# 03-PeripheralPart-V2_1.net
KiCad netlist of a schematic drawn in Altium Designer
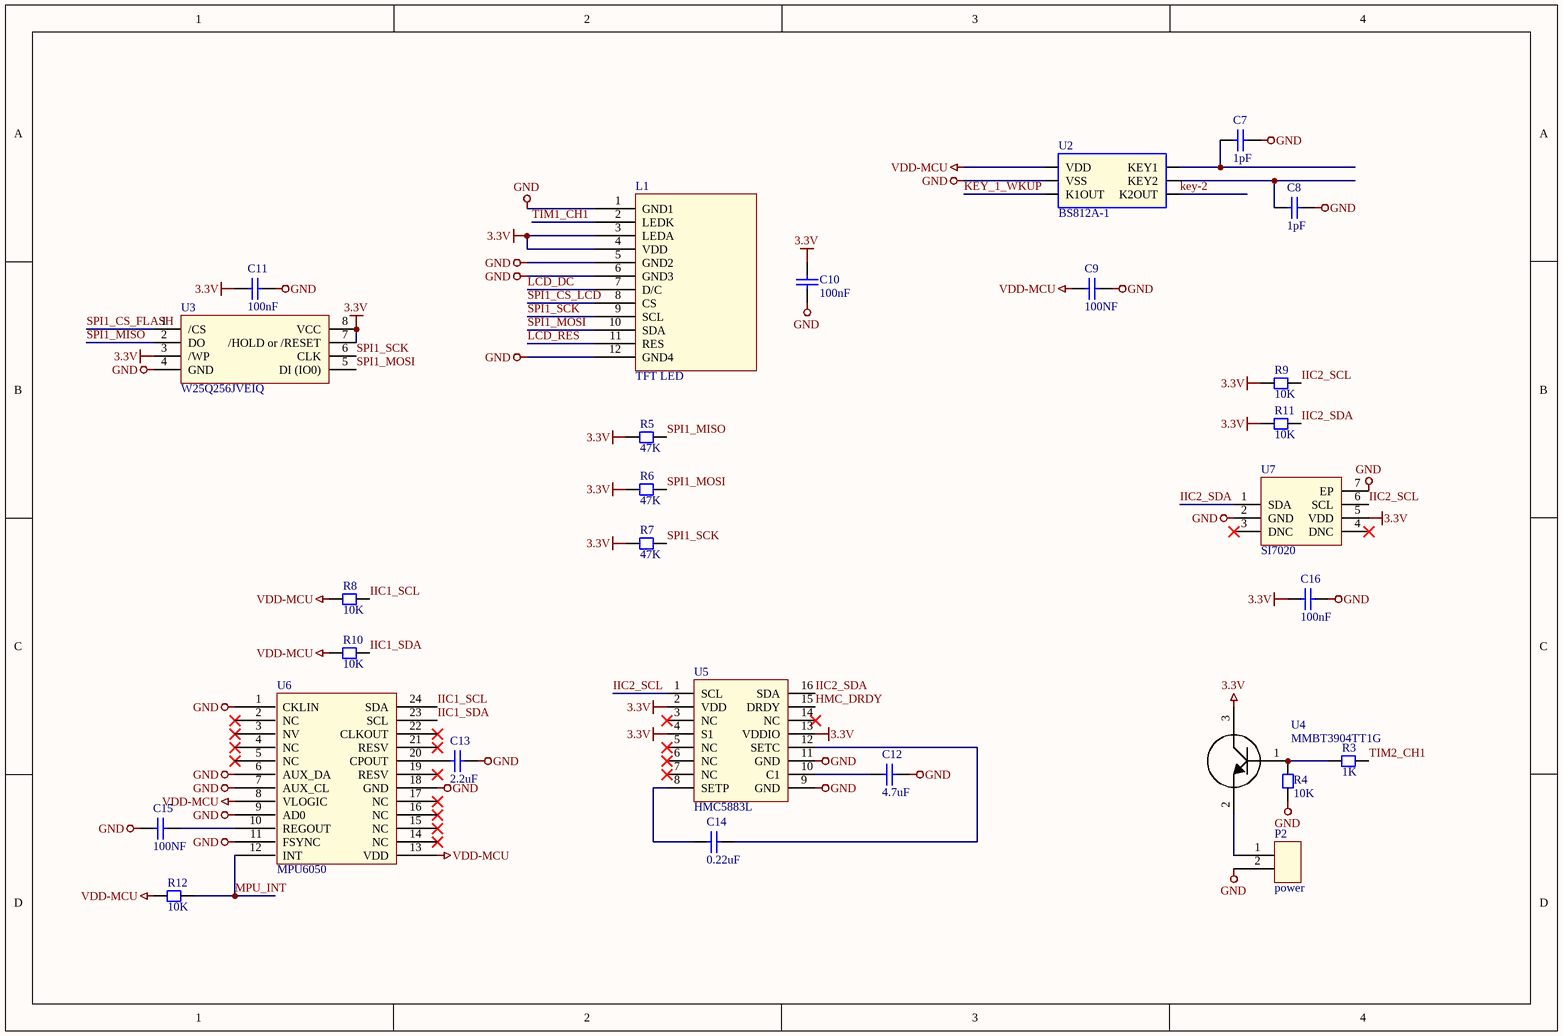
[diagram p0: 03-PeripheralPart-V2.1.SchDoc]

(export (version "E")
  (design (tool "Eeschema 10.0.6"))
  (components
    (comp (ref "C7")
      (value "1pF")
      (footprint "CC1005-0402")
      (description "贴片电容")
      (libsource (lib "tianxiaohua_Schlib") (part "Chip capacitor"))
    )
    (comp (ref "C8")
      (value "1pF")
      (footprint "CC1005-0402")
      (description "贴片电容")
      (libsource (lib "tianxiaohua_Schlib") (part "Chip capacitor"))
    )
    (comp (ref "C9")
      (value "100NF")
      (footprint "CC1005-0402")
      (description "贴片电容")
      (libsource (lib "tianxiaohua_Schlib") (part "Chip capacitor"))
    )
    (comp (ref "C10")
      (value "100nF")
      (footprint "CC1005-0402")
      (description "贴片电容")
      (libsource (lib "tianxiaohua_Schlib") (part "Chip capacitor"))
    )
    (comp (ref "C11")
      (value "100nF")
      (footprint "CC1005-0402")
      (description "贴片电容")
      (libsource (lib "tianxiaohua_Schlib") (part "Chip capacitor"))
    )
    (comp (ref "C12")
      (value "4.7uF")
      (footprint "CC1005-0402")
      (description "贴片电容")
      (libsource (lib "tianxiaohua_Schlib") (part "Chip capacitor"))
    )
    (comp (ref "C13")
      (value "2.2uF")
      (footprint "CC1005-0402")
      (description "贴片电容")
      (libsource (lib "tianxiaohua_Schlib") (part "Chip capacitor"))
    )
    (comp (ref "C14")
      (value "0.22uF")
      (footprint "CC1005-0402")
      (description "贴片电容")
      (libsource (lib "tianxiaohua_Schlib") (part "Chip capacitor"))
    )
    (comp (ref "C15")
      (value "100NF")
      (footprint "CC1005-0402")
      (description "贴片电容")
      (libsource (lib "tianxiaohua_Schlib") (part "Chip capacitor"))
    )
    (comp (ref "C16")
      (value "100nF")
      (footprint "CC1005-0402")
      (description "贴片电容")
      (libsource (lib "tianxiaohua_Schlib") (part "Chip capacitor"))
    )
    (comp (ref "L1")
      (value "TFT LED")
      (footprint "LCD-1.3-(2)")
      (description "1.3寸显示屏幕")
      (libsource (lib "tianxiaohua_Schlib") (part "LCD-IPSscreen-1.3"))
    )
    (comp (ref "P2")
      (value "power")
      (footprint "POWER-3.7V")
      (libsource (lib "tianxiaohua_Schlib") (part "power"))
    )
    (comp (ref "R3")
      (value "1K")
      (footprint "CR1005-0402")
      (description "贴片电阻")
      (libsource (lib "tianxiaohua_Schlib") (part "Chip resistor"))
    )
    (comp (ref "R4")
      (value "10K")
      (footprint "CR1005-0402")
      (description "贴片电阻")
      (libsource (lib "") (part "Chip resistor_1"))
    )
    (comp (ref "R5")
      (value "47K")
      (footprint "CR1005-0402")
      (description "贴片电阻")
      (libsource (lib "tianxiaohua_Schlib") (part "Chip resistor"))
    )
    (comp (ref "R6")
      (value "47K")
      (footprint "CR1005-0402")
      (description "贴片电阻")
      (libsource (lib "tianxiaohua_Schlib") (part "Chip resistor"))
    )
    (comp (ref "R7")
      (value "47K")
      (footprint "CR1005-0402")
      (description "贴片电阻")
      (libsource (lib "tianxiaohua_Schlib") (part "Chip resistor"))
    )
    (comp (ref "R8")
      (value "10K")
      (footprint "CR1005-0402")
      (description "贴片电阻")
      (libsource (lib "tianxiaohua_Schlib") (part "Chip resistor"))
    )
    (comp (ref "R9")
      (value "10K")
      (footprint "CR1005-0402")
      (description "贴片电阻")
      (libsource (lib "tianxiaohua_Schlib") (part "Chip resistor"))
    )
    (comp (ref "R10")
      (value "10K")
      (footprint "CR1005-0402")
      (description "贴片电阻")
      (libsource (lib "tianxiaohua_Schlib") (part "Chip resistor"))
    )
    (comp (ref "R11")
      (value "10K")
      (footprint "CR1005-0402")
      (description "贴片电阻")
      (libsource (lib "tianxiaohua_Schlib") (part "Chip resistor"))
    )
    (comp (ref "R12")
      (value "10K")
      (footprint "CR1005-0402")
      (description "贴片电阻")
      (libsource (lib "tianxiaohua_Schlib") (part "Chip resistor"))
    )
    (comp (ref "U2")
      (value "BS812A-1")
      (footprint "SOT23-6")
      (description "触摸按键 两路 SOP23-6封装极简电路")
      (libsource (lib "tianxiaohua_Schlib") (part "BS812A-1"))
    )
    (comp (ref "U3")
      (value "W25Q256JVEIQ")
      (footprint "WSON-8_L8.0-W6.10-P1.27-TL-EP")
      (description "FLASH")
      (libsource (lib "tianxiaohua_Schlib") (part "W25Q256JVEIQ"))
    )
    (comp (ref "U4")
      (value "MMBT3904TT1G")
      (footprint "SOT-416")
      (description "NPN 电流 - 集电极（Ic）（最大值）：200mA 电压 - 集射极击穿（最大值）：40V SOT-23-3")
      (libsource (lib "tianxiaohua_Schlib") (part "MMBT3904TT1G"))
    )
    (comp (ref "U5")
      (value "HMC5883L")
      (footprint "LPCC-16_L3.0-W3.0-P0.50-BL")
      (description "三轴罗盘")
      (libsource (lib "tianxiaohua_Schlib") (part "HMC5883L"))
    )
    (comp (ref "U6")
      (value "MPU6050")
      (footprint "QFN24 - duplicate")
      (description "陀螺仪")
      (libsource (lib "tianxiaohua_Schlib") (part "MPU6050"))
    )
    (comp (ref "U7")
      (value "SI7020")
      (footprint "DFN-6")
      (description "温湿度传感器芯片")
      (libsource (lib "tianxiaohua_Schlib") (part "SI7020"))
    )
  )
  (nets
    (net (code "1") (name "/HMC_DRDY") (class "Default")
      (node (ref "U5") (pin "15") (pinfunction "DRDY_15") (pintype "passive"))
    )
    (net (code "2") (name "/IIC1_SCL") (class "Default")
      (node (ref "R8") (pin "1") (pinfunction "1_1") (pintype "passive"))
      (node (ref "U6") (pin "24") (pinfunction "SDA_24") (pintype "passive"))
    )
    (net (code "3") (name "/IIC1_SDA") (class "Default")
      (node (ref "R10") (pin "1") (pinfunction "1_1") (pintype "passive"))
      (node (ref "U6") (pin "23") (pinfunction "SCL_23") (pintype "passive"))
    )
    (net (code "4") (name "/IIC2_SCL") (class "Default")
      (node (ref "R9") (pin "1") (pinfunction "1_1") (pintype "passive"))
      (node (ref "U5") (pin "1") (pinfunction "SCL_1") (pintype "passive"))
      (node (ref "U7") (pin "6") (pinfunction "SCL_6") (pintype "passive"))
    )
    (net (code "5") (name "/IIC2_SDA") (class "Default")
      (node (ref "R11") (pin "1") (pinfunction "1_1") (pintype "passive"))
      (node (ref "U5") (pin "16") (pinfunction "SDA_16") (pintype "passive"))
      (node (ref "U7") (pin "1") (pinfunction "SDA_1") (pintype "passive"))
    )
    (net (code "6") (name "/KEY_1_WKUP") (class "Default")
      (node (ref "U2") (pin "3") (pinfunction "K1OUT_3") (pintype "passive"))
    )
    (net (code "7") (name "/LCD_DC") (class "Default")
      (node (ref "L1") (pin "7") (pinfunction "D/C_7") (pintype "passive"))
    )
    (net (code "8") (name "/LCD_RES") (class "Default")
      (node (ref "L1") (pin "11") (pinfunction "RES_11") (pintype "passive"))
    )
    (net (code "9") (name "/MPU_INT") (class "Default")
      (node (ref "R12") (pin "1") (pinfunction "1_1") (pintype "passive"))
      (node (ref "U6") (pin "12") (pinfunction "INT_12") (pintype "passive"))
    )
    (net (code "10") (name "/SPI1_CS_FLASH") (class "Default")
      (node (ref "U3") (pin "1") (pinfunction "/CS_1") (pintype "passive"))
    )
    (net (code "11") (name "/SPI1_CS_LCD") (class "Default")
      (node (ref "L1") (pin "8") (pinfunction "CS_8") (pintype "passive"))
    )
    (net (code "12") (name "/SPI1_MISO") (class "Default")
      (node (ref "R5") (pin "1") (pinfunction "1_1") (pintype "passive"))
      (node (ref "U3") (pin "2") (pinfunction "DO_2") (pintype "passive"))
    )
    (net (code "13") (name "/SPI1_MOSI") (class "Default")
      (node (ref "L1") (pin "10") (pinfunction "SDA_10") (pintype "passive"))
      (node (ref "R6") (pin "1") (pinfunction "1_1") (pintype "passive"))
      (node (ref "U3") (pin "5") (pinfunction "DI_(IO0)_5") (pintype "passive"))
    )
    (net (code "14") (name "/SPI1_SCK") (class "Default")
      (node (ref "L1") (pin "9") (pinfunction "SCL_9") (pintype "passive"))
      (node (ref "R7") (pin "1") (pinfunction "1_1") (pintype "passive"))
      (node (ref "U3") (pin "6") (pinfunction "CLK_6") (pintype "passive"))
    )
    (net (code "15") (name "/TIM1_CH1") (class "Default")
      (node (ref "L1") (pin "2") (pinfunction "LEDK_2") (pintype "passive"))
    )
    (net (code "16") (name "/TIM2_CH1") (class "Default")
      (node (ref "R3") (pin "1") (pinfunction "1_1") (pintype "passive"))
    )
    (net (code "17") (name "/key-2") (class "Default")
      (node (ref "U2") (pin "4") (pinfunction "K2OUT_4") (pintype "passive"))
    )
    (net (code "18") (name "3.3V") (class "Default")
      (node (ref "C10") (pin "1") (pinfunction "1_1") (pintype "passive"))
      (node (ref "C11") (pin "1") (pinfunction "1_1") (pintype "passive"))
      (node (ref "C16") (pin "1") (pinfunction "1_1") (pintype "passive"))
      (node (ref "L1") (pin "3") (pinfunction "LEDA_3") (pintype "passive"))
      (node (ref "L1") (pin "4") (pinfunction "VDD_4") (pintype "passive"))
      (node (ref "R11") (pin "2") (pinfunction "2_2") (pintype "passive"))
      (node (ref "R5") (pin "2") (pinfunction "2_2") (pintype "passive"))
      (node (ref "R6") (pin "2") (pinfunction "2_2") (pintype "passive"))
      (node (ref "R7") (pin "2") (pinfunction "2_2") (pintype "passive"))
      (node (ref "R9") (pin "2") (pinfunction "2_2") (pintype "passive"))
      (node (ref "U3") (pin "3") (pinfunction "/WP_3") (pintype "passive"))
      (node (ref "U3") (pin "7") (pinfunction "/HOLD_or_/RESET_7") (pintype "passive"))
      (node (ref "U3") (pin "8") (pinfunction "VCC_8") (pintype "passive"))
      (node (ref "U4") (pin "3") (pinfunction "3_3") (pintype "passive"))
      (node (ref "U5") (pin "13") (pinfunction "VDDIO_13") (pintype "passive"))
      (node (ref "U5") (pin "2") (pinfunction "VDD_2") (pintype "passive"))
      (node (ref "U5") (pin "4") (pinfunction "S1_4") (pintype "passive"))
      (node (ref "U7") (pin "5") (pinfunction "VDD_5") (pintype "passive"))
    )
    (net (code "19") (name "GND") (class "Default")
      (node (ref "C10") (pin "2") (pinfunction "2_2") (pintype "passive"))
      (node (ref "C11") (pin "2") (pinfunction "2_2") (pintype "passive"))
      (node (ref "C12") (pin "2") (pinfunction "2_2") (pintype "passive"))
      (node (ref "C13") (pin "2") (pinfunction "2_2") (pintype "passive"))
      (node (ref "C15") (pin "1") (pinfunction "1_1") (pintype "passive"))
      (node (ref "C16") (pin "2") (pinfunction "2_2") (pintype "passive"))
      (node (ref "C7") (pin "2") (pinfunction "2_2") (pintype "passive"))
      (node (ref "C8") (pin "2") (pinfunction "2_2") (pintype "passive"))
      (node (ref "C9") (pin "1") (pinfunction "1_1") (pintype "passive"))
      (node (ref "L1") (pin "1") (pinfunction "GND1_1") (pintype "passive"))
      (node (ref "L1") (pin "12") (pinfunction "GND4_12") (pintype "passive"))
      (node (ref "L1") (pin "5") (pinfunction "GND2_5") (pintype "passive"))
      (node (ref "L1") (pin "6") (pinfunction "GND3_6") (pintype "passive"))
      (node (ref "P2") (pin "2") (pinfunction "2_2") (pintype "passive"))
      (node (ref "R4") (pin "2") (pinfunction "2_2") (pintype "passive"))
      (node (ref "U2") (pin "2") (pinfunction "VSS_2") (pintype "passive"))
      (node (ref "U3") (pin "4") (pinfunction "GND_4") (pintype "passive"))
      (node (ref "U5") (pin "11") (pinfunction "GND_11") (pintype "passive"))
      (node (ref "U5") (pin "9") (pinfunction "GND_9") (pintype "passive"))
      (node (ref "U6") (pin "1") (pinfunction "CKLIN_1") (pintype "passive"))
      (node (ref "U6") (pin "11") (pinfunction "FSYNC_11") (pintype "passive"))
      (node (ref "U6") (pin "18") (pinfunction "GND_18") (pintype "passive"))
      (node (ref "U6") (pin "6") (pinfunction "AUX_DA_6") (pintype "passive"))
      (node (ref "U6") (pin "7") (pinfunction "AUX_CL_7") (pintype "passive"))
      (node (ref "U6") (pin "9") (pinfunction "AD0_9") (pintype "passive"))
      (node (ref "U7") (pin "2") (pinfunction "GND_2") (pintype "passive"))
      (node (ref "U7") (pin "7") (pinfunction "EP_7") (pintype "passive"))
    )
    (net (code "20") (name "Net-(P2-Pad1)") (class "Default")
      (node (ref "P2") (pin "1") (pinfunction "1_1") (pintype "passive"))
      (node (ref "U4") (pin "2") (pinfunction "2_2") (pintype "passive"))
    )
    (net (code "21") (name "Net-(R3-Pad2)") (class "Default")
      (node (ref "R3") (pin "2") (pinfunction "2_2") (pintype "passive"))
      (node (ref "R4") (pin "1") (pinfunction "1_1") (pintype "passive"))
      (node (ref "U4") (pin "1") (pinfunction "1_1") (pintype "passive"))
    )
    (net (code "22") (name "Net-(U2-KEY1)") (class "Default")
      (node (ref "C7") (pin "1") (pinfunction "1_1") (pintype "passive"))
      (node (ref "U2") (pin "6") (pinfunction "KEY1_6") (pintype "passive"))
    )
    (net (code "23") (name "Net-(U2-KEY2)") (class "Default")
      (node (ref "C8") (pin "1") (pinfunction "1_1") (pintype "passive"))
      (node (ref "U2") (pin "5") (pinfunction "KEY2_5") (pintype "passive"))
    )
    (net (code "24") (name "Net-(U5-C1)") (class "Default")
      (node (ref "C12") (pin "1") (pinfunction "1_1") (pintype "passive"))
      (node (ref "U5") (pin "10") (pinfunction "C1_10") (pintype "passive"))
    )
    (net (code "25") (name "Net-(U5-SETC)") (class "Default")
      (node (ref "C14") (pin "2") (pinfunction "2_2") (pintype "passive"))
      (node (ref "U5") (pin "12") (pinfunction "SETC_12") (pintype "passive"))
    )
    (net (code "26") (name "Net-(U5-SETP)") (class "Default")
      (node (ref "C14") (pin "1") (pinfunction "1_1") (pintype "passive"))
      (node (ref "U5") (pin "8") (pinfunction "SETP_8") (pintype "passive"))
    )
    (net (code "27") (name "Net-(U6-CPOUT)") (class "Default")
      (node (ref "C13") (pin "1") (pinfunction "1_1") (pintype "passive"))
      (node (ref "U6") (pin "20") (pinfunction "CPOUT_20") (pintype "passive"))
    )
    (net (code "28") (name "Net-(U6-REGOUT)") (class "Default")
      (node (ref "C15") (pin "2") (pinfunction "2_2") (pintype "passive"))
      (node (ref "U6") (pin "10") (pinfunction "REGOUT_10") (pintype "passive"))
    )
    (net (code "29") (name "VDD-MCU") (class "Default")
      (node (ref "C9") (pin "2") (pinfunction "2_2") (pintype "passive"))
      (node (ref "R10") (pin "2") (pinfunction "2_2") (pintype "passive"))
      (node (ref "R12") (pin "2") (pinfunction "2_2") (pintype "passive"))
      (node (ref "R8") (pin "2") (pinfunction "2_2") (pintype "passive"))
      (node (ref "U2") (pin "1") (pinfunction "VDD_1") (pintype "passive"))
      (node (ref "U6") (pin "13") (pinfunction "VDD_13") (pintype "passive"))
      (node (ref "U6") (pin "8") (pinfunction "VLOGIC_8") (pintype "passive"))
    )
    (net (code "30") (name "unconnected-(U5-NC-Pad3)") (class "Default")
      (node (ref "U5") (pin "3") (pinfunction "NC_3") (pintype "passive+no_connect"))
    )
    (net (code "31") (name "unconnected-(U5-NC-Pad5)") (class "Default")
      (node (ref "U5") (pin "5") (pinfunction "NC_5") (pintype "passive+no_connect"))
    )
    (net (code "32") (name "unconnected-(U5-NC-Pad6)") (class "Default")
      (node (ref "U5") (pin "6") (pinfunction "NC_6") (pintype "passive+no_connect"))
    )
    (net (code "33") (name "unconnected-(U5-NC-Pad7)") (class "Default")
      (node (ref "U5") (pin "7") (pinfunction "NC_7") (pintype "passive+no_connect"))
    )
    (net (code "34") (name "unconnected-(U5-NC-Pad14)") (class "Default")
      (node (ref "U5") (pin "14") (pinfunction "NC_14") (pintype "passive+no_connect"))
    )
    (net (code "35") (name "unconnected-(U6-CLKOUT-Pad22)") (class "Default")
      (node (ref "U6") (pin "22") (pinfunction "CLKOUT_22") (pintype "passive+no_connect"))
    )
    (net (code "36") (name "unconnected-(U6-NC-Pad2)") (class "Default")
      (node (ref "U6") (pin "2") (pinfunction "NC_2") (pintype "passive+no_connect"))
    )
    (net (code "37") (name "unconnected-(U6-NC-Pad4)") (class "Default")
      (node (ref "U6") (pin "4") (pinfunction "NC_4") (pintype "passive+no_connect"))
    )
    (net (code "38") (name "unconnected-(U6-NC-Pad5)") (class "Default")
      (node (ref "U6") (pin "5") (pinfunction "NC_5") (pintype "passive+no_connect"))
    )
    (net (code "39") (name "unconnected-(U6-NC-Pad14)") (class "Default")
      (node (ref "U6") (pin "14") (pinfunction "NC_14") (pintype "passive+no_connect"))
    )
    (net (code "40") (name "unconnected-(U6-NC-Pad15)") (class "Default")
      (node (ref "U6") (pin "15") (pinfunction "NC_15") (pintype "passive+no_connect"))
    )
    (net (code "41") (name "unconnected-(U6-NC-Pad16)") (class "Default")
      (node (ref "U6") (pin "16") (pinfunction "NC_16") (pintype "passive+no_connect"))
    )
    (net (code "42") (name "unconnected-(U6-NC-Pad17)") (class "Default")
      (node (ref "U6") (pin "17") (pinfunction "NC_17") (pintype "passive+no_connect"))
    )
    (net (code "43") (name "unconnected-(U6-NV-Pad3)") (class "Default")
      (node (ref "U6") (pin "3") (pinfunction "NV_3") (pintype "passive+no_connect"))
    )
    (net (code "44") (name "unconnected-(U6-RESV-Pad19)") (class "Default")
      (node (ref "U6") (pin "19") (pinfunction "RESV_19") (pintype "passive+no_connect"))
    )
    (net (code "45") (name "unconnected-(U6-RESV-Pad21)") (class "Default")
      (node (ref "U6") (pin "21") (pinfunction "RESV_21") (pintype "passive+no_connect"))
    )
    (net (code "46") (name "unconnected-(U7-DNC-Pad3)") (class "Default")
      (node (ref "U7") (pin "3") (pinfunction "DNC_3") (pintype "passive+no_connect"))
    )
    (net (code "47") (name "unconnected-(U7-DNC-Pad4)") (class "Default")
      (node (ref "U7") (pin "4") (pinfunction "DNC_4") (pintype "passive+no_connect"))
    )
  )
)
